# 02_-_RS232.net
KiCad netlist of a schematic drawn in Altium Designer
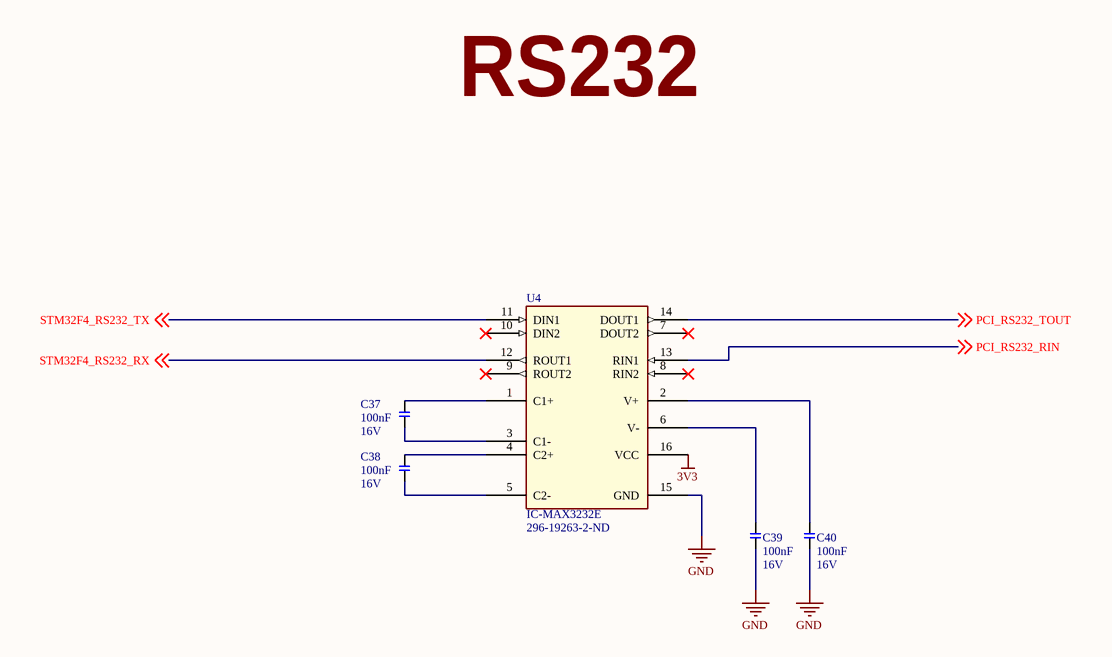
[diagram p0: [02] - RS232.SchDoc]

(export (version "E")
  (design (tool "Eeschema 10.0.6"))
  (components
    (comp (ref "C37")
      (value "100nF")
      (footprint "C0805")
      (description "AVX - 0805YA103JAT2A - CAP, MLCC, C0G/NP0, 10NF, 16V, 0805")
      (fields
        (field (name "MANUFACTURER") "AVX")
        (field (name "MANUFACTURER PART NUMBER") "0805YA103JAT2A")
        (field (name "VOLTAGE - RATED") "16V")
      )
      (libsource (lib "CPU_STM_080816") (part "C-100NF,16V,0805"))
    )
    (comp (ref "C38")
      (value "100nF")
      (footprint "C0805")
      (description "AVX - 0805YA103JAT2A - CAP, MLCC, C0G/NP0, 10NF, 16V, 0805")
      (fields
        (field (name "MANUFACTURER") "AVX")
        (field (name "MANUFACTURER PART NUMBER") "0805YA103JAT2A")
        (field (name "VOLTAGE - RATED") "16V")
      )
      (libsource (lib "CPU_STM_080816") (part "C-100NF,16V,0805"))
    )
    (comp (ref "C39")
      (value "100nF")
      (footprint "C0805")
      (description "AVX - 0805YA103JAT2A - CAP, MLCC, C0G/NP0, 10NF, 16V, 0805")
      (fields
        (field (name "MANUFACTURER") "AVX")
        (field (name "MANUFACTURER PART NUMBER") "0805YA103JAT2A")
        (field (name "VOLTAGE - RATED") "16V")
      )
      (libsource (lib "CPU_STM_080816") (part "C-100NF,16V,0805"))
    )
    (comp (ref "C40")
      (value "100nF")
      (footprint "C0805")
      (description "AVX - 0805YA103JAT2A - CAP, MLCC, C0G/NP0, 10NF, 16V, 0805")
      (fields
        (field (name "MANUFACTURER") "AVX")
        (field (name "MANUFACTURER PART NUMBER") "0805YA103JAT2A")
        (field (name "VOLTAGE - RATED") "16V")
      )
      (libsource (lib "CPU_STM_080816") (part "C-100NF,16V,0805"))
    )
    (comp (ref "U4")
      (value "IC-MAX3232E")
      (footprint "TI-DW16_M")
      (description "Dual Channel RS-232 Line Driver/Receiver")
      (fields
        (field (name "TIINTPARTNUMBER") "1A0213")
        (field (name "MFR") "TI")
        (field (name "SUPPLIER PART NUMBER 1") "296-19263-2-ND")
      )
      (libsource (lib "CPU_STM_080816") (part "IC-MAX3232E"))
    )
  )
  (nets
    (net (code "1") (name "3V3") (class "Default")
      (node (ref "U4") (pin "16") (pinfunction "VCC_16") (pintype "power_in"))
    )
    (net (code "2") (name "GND") (class "Default")
      (node (ref "C39") (pin "1") (pinfunction "1_1") (pintype "passive"))
      (node (ref "C40") (pin "1") (pinfunction "1_1") (pintype "passive"))
      (node (ref "U4") (pin "15") (pinfunction "GND_15") (pintype "power_in"))
    )
    (net (code "3") (name "Net-(U4-C1+)") (class "Default")
      (node (ref "C37") (pin "2") (pinfunction "2_2") (pintype "passive"))
      (node (ref "U4") (pin "1") (pinfunction "C1+_1") (pintype "passive"))
    )
    (net (code "4") (name "Net-(U4-C1-)") (class "Default")
      (node (ref "C37") (pin "1") (pinfunction "1_1") (pintype "passive"))
      (node (ref "U4") (pin "3") (pinfunction "C1-_3") (pintype "passive"))
    )
    (net (code "5") (name "Net-(U4-C2+)") (class "Default")
      (node (ref "C38") (pin "2") (pinfunction "2_2") (pintype "passive"))
      (node (ref "U4") (pin "4") (pinfunction "C2+_4") (pintype "passive"))
    )
    (net (code "6") (name "Net-(U4-C2-)") (class "Default")
      (node (ref "C38") (pin "1") (pinfunction "1_1") (pintype "passive"))
      (node (ref "U4") (pin "5") (pinfunction "C2-_5") (pintype "passive"))
    )
    (net (code "7") (name "Net-(U4-V+)") (class "Default")
      (node (ref "C40") (pin "2") (pinfunction "2_2") (pintype "passive"))
      (node (ref "U4") (pin "2") (pinfunction "V+_2") (pintype "passive"))
    )
    (net (code "8") (name "Net-(U4-V-)") (class "Default")
      (node (ref "C39") (pin "2") (pinfunction "2_2") (pintype "passive"))
      (node (ref "U4") (pin "6") (pinfunction "V-_6") (pintype "passive"))
    )
    (net (code "9") (name "PCI_RS232_RIN") (class "Default")
      (node (ref "U4") (pin "13") (pinfunction "RIN1_13") (pintype "input"))
    )
    (net (code "10") (name "PCI_RS232_TOUT") (class "Default")
      (node (ref "U4") (pin "14") (pinfunction "DOUT1_14") (pintype "output"))
    )
    (net (code "11") (name "STM32F4_RS232_RX") (class "Default")
      (node (ref "U4") (pin "12") (pinfunction "ROUT1_12") (pintype "output"))
    )
    (net (code "12") (name "STM32F4_RS232_TX") (class "Default")
      (node (ref "U4") (pin "11") (pinfunction "DIN1_11") (pintype "input"))
    )
    (net (code "13") (name "unconnected-(U4-DIN2-Pad10)") (class "Default")
      (node (ref "U4") (pin "10") (pinfunction "DIN2_10") (pintype "input+no_connect"))
    )
    (net (code "14") (name "unconnected-(U4-DOUT2-Pad7)") (class "Default")
      (node (ref "U4") (pin "7") (pinfunction "DOUT2_7") (pintype "output+no_connect"))
    )
    (net (code "15") (name "unconnected-(U4-RIN2-Pad8)") (class "Default")
      (node (ref "U4") (pin "8") (pinfunction "RIN2_8") (pintype "input+no_connect"))
    )
    (net (code "16") (name "unconnected-(U4-ROUT2-Pad9)") (class "Default")
      (node (ref "U4") (pin "9") (pinfunction "ROUT2_9") (pintype "output+no_connect"))
    )
  )
)
